# STM32-PROX_2.net
KiCad netlist of a schematic drawn in Altium Designer
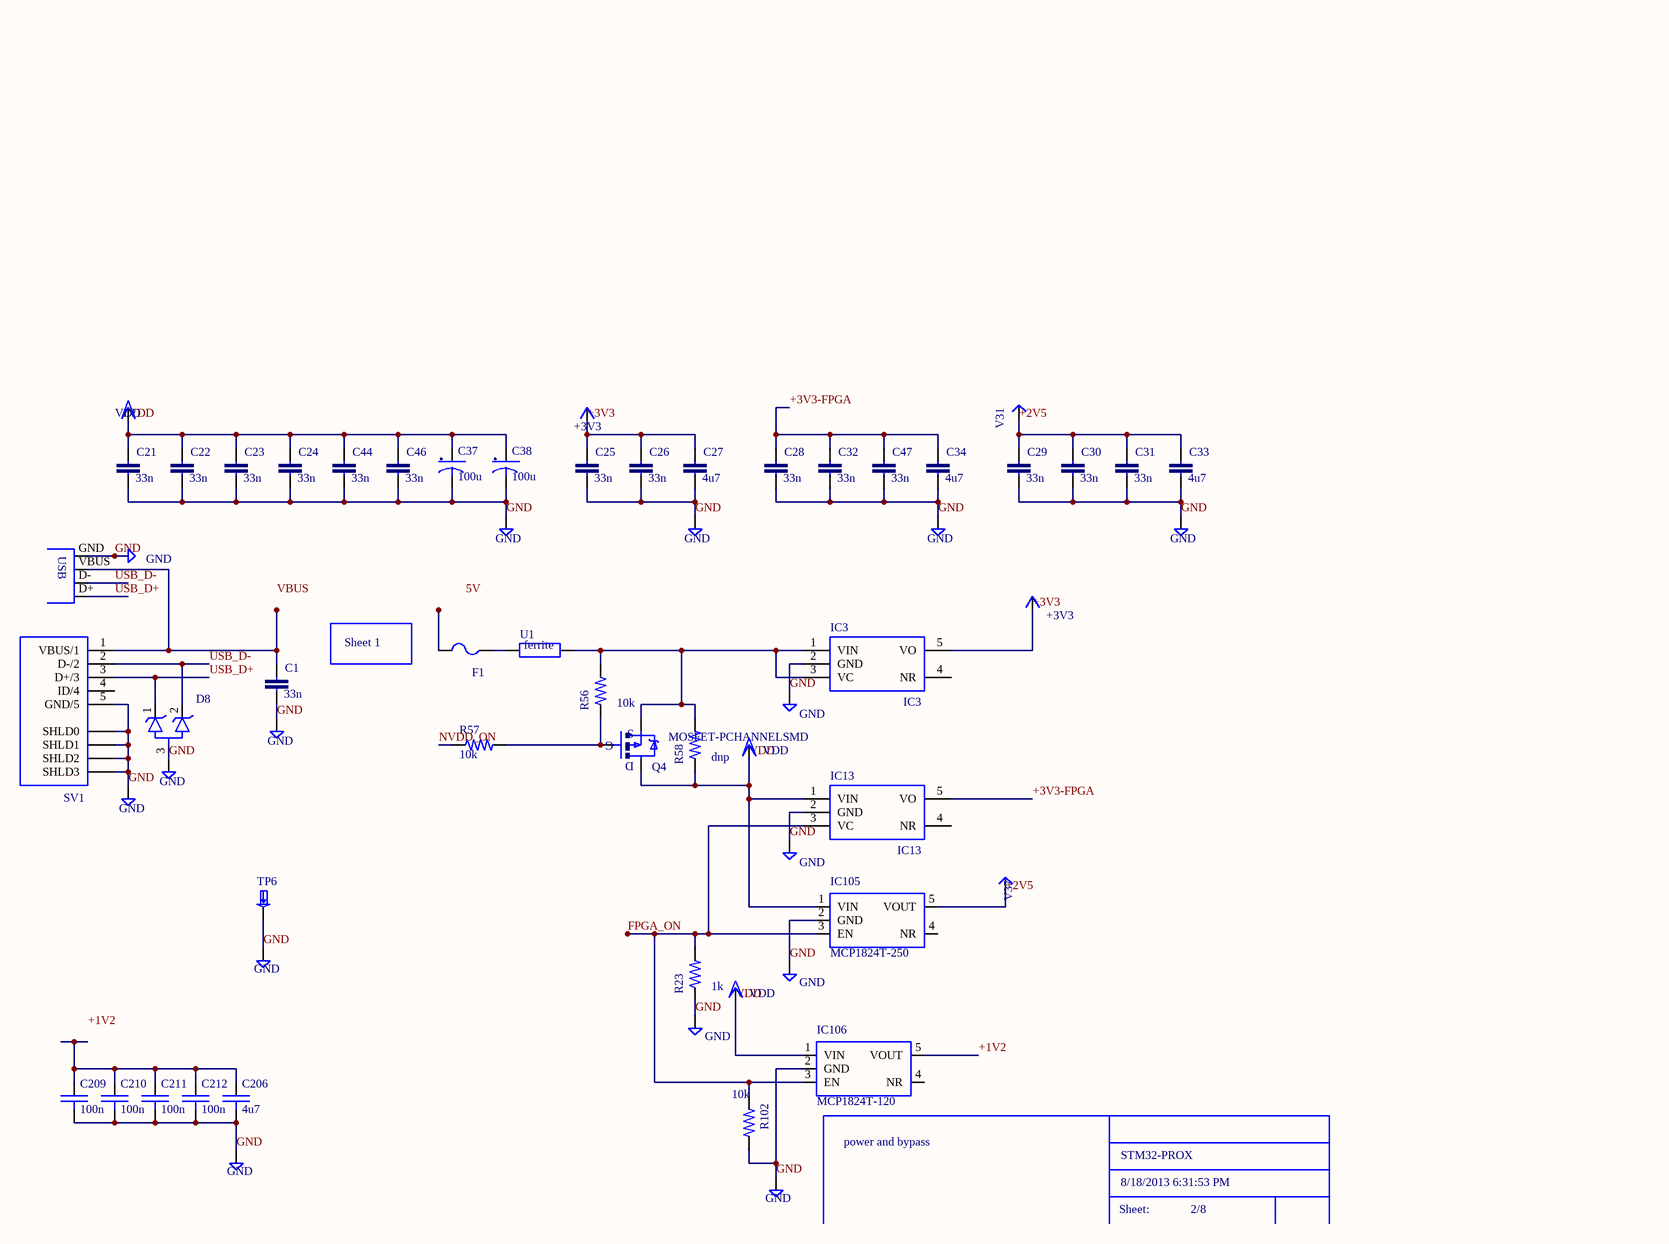
[diagram p0: STM32-PROX_2.SchDoc]

(export (version "E")
  (design (tool "Eeschema 10.0.6"))
  (components
    (comp (ref "C1")
      (value "33n")
      (footprint "RLC_0603")
      (libsource (lib "STM32-PROX") (part "CAPACITORRLC_0603"))
    )
    (comp (ref "C21")
      (value "33n")
      (footprint "RLC_0603")
      (libsource (lib "STM32-PROX") (part "CAPACITORRLC_0603"))
    )
    (comp (ref "C22")
      (value "33n")
      (footprint "RLC_0603")
      (libsource (lib "STM32-PROX") (part "CAPACITORRLC_0603"))
    )
    (comp (ref "C23")
      (value "33n")
      (footprint "RLC_0603")
      (libsource (lib "STM32-PROX") (part "CAPACITORRLC_0603"))
    )
    (comp (ref "C24")
      (value "33n")
      (footprint "RLC_0603")
      (libsource (lib "STM32-PROX") (part "CAPACITORRLC_0603"))
    )
    (comp (ref "C25")
      (value "33n")
      (footprint "RLC_0603")
      (libsource (lib "STM32-PROX") (part "CAPACITORRLC_0603"))
    )
    (comp (ref "C26")
      (value "33n")
      (footprint "RLC_0603")
      (libsource (lib "STM32-PROX") (part "CAPACITORRLC_0603"))
    )
    (comp (ref "C27")
      (value "4u7")
      (footprint "RLC_1210")
      (libsource (lib "STM32-PROX") (part "CAPACITOR1210"))
    )
    (comp (ref "C28")
      (value "33n")
      (footprint "RLC_0603")
      (libsource (lib "STM32-PROX") (part "CAPACITORRLC_0603"))
    )
    (comp (ref "C29")
      (value "33n")
      (footprint "RLC_0603")
      (libsource (lib "STM32-PROX") (part "CAPACITORRLC_0603"))
    )
    (comp (ref "C30")
      (value "33n")
      (footprint "RLC_0603")
      (libsource (lib "STM32-PROX") (part "CAPACITORRLC_0603"))
    )
    (comp (ref "C31")
      (value "33n")
      (footprint "RLC_0603")
      (libsource (lib "STM32-PROX") (part "CAPACITORRLC_0603"))
    )
    (comp (ref "C32")
      (value "33n")
      (footprint "RLC_0603")
      (libsource (lib "STM32-PROX") (part "CAPACITORRLC_0603"))
    )
    (comp (ref "C33")
      (value "4u7")
      (footprint "RLC_1210")
      (libsource (lib "STM32-PROX") (part "CAPACITOR1210"))
    )
    (comp (ref "C34")
      (value "4u7")
      (footprint "RLC_1210")
      (libsource (lib "STM32-PROX") (part "CAPACITOR1210"))
    )
    (comp (ref "C37")
      (value "100u")
      (footprint "D/7343-31R")
      (libsource (lib "STM32-PROX") (part "CPOL-USD/7343-31R"))
    )
    (comp (ref "C38")
      (value "100u")
      (footprint "D/7343-31R")
      (libsource (lib "STM32-PROX") (part "CPOL-USD/7343-31R"))
    )
    (comp (ref "C44")
      (value "33n")
      (footprint "RLC_0603")
      (libsource (lib "STM32-PROX") (part "CAPACITORRLC_0603"))
    )
    (comp (ref "C46")
      (value "33n")
      (footprint "RLC_0603")
      (libsource (lib "STM32-PROX") (part "CAPACITORRLC_0603"))
    )
    (comp (ref "C47")
      (value "33n")
      (footprint "RLC_0603")
      (libsource (lib "STM32-PROX") (part "CAPACITORRLC_0603"))
    )
    (comp (ref "C206") (value "4u7") (footprint "RLC_0603") (libsource (lib "STM32-PROX") (part "C-EU")))
    (comp (ref "C209") (value "100n") (footprint "RLC_0603") (libsource (lib "STM32-PROX") (part "C-EU")))
    (comp (ref "C210") (value "100n") (footprint "RLC_0603") (libsource (lib "STM32-PROX") (part "C-EU")))
    (comp (ref "C211") (value "100n") (footprint "RLC_0603") (libsource (lib "STM32-PROX") (part "C-EU")))
    (comp (ref "C212") (value "100n") (footprint "RLC_0603") (libsource (lib "STM32-PROX") (part "C-EU")))
    (comp (ref "D8")
      (value "~")
      (footprint "SOT23-3LEAD")
      (libsource (lib "STM32-PROX") (part "DUAL-TVS-COMMON-ANODE"))
    )
    (comp (ref "F1") (value "~") (footprint "1812") (libsource (lib "STM32-PROX") (part "PTCFUSE-1812")))
    (comp (ref "FRAME1") (value "~") (libsource (lib "STM32-PROX") (part "A4L-LOC")))
    (comp (ref "IC3")
      (value "~")
      (footprint "SOT-23-5")
      (libsource (lib "STM32-PROX") (part "PQ1X331M2ZP-3V3-LDO-SOT-23-5"))
    )
    (comp (ref "IC13")
      (value "~")
      (footprint "SOT-23-5")
      (libsource (lib "STM32-PROX") (part "PQ1X331M2ZP-3V3-LDO-SOT-23-5"))
    )
    (comp (ref "IC105")
      (value "MCP1824T-250")
      (footprint "SOT-23-5")
      (libsource (lib "STM32-PROX") (part "TPS79925"))
    )
    (comp (ref "IC106")
      (value "MCP1824T-120")
      (footprint "SOT-23-5")
      (libsource (lib "STM32-PROX") (part "TPS79912"))
    )
    (comp (ref "Q4")
      (value "MOSFET-PCHANNELSMD")
      (footprint "SOT23-3")
      (libsource (lib "STM32-PROX") (part "MOSFET-PCHANNELSMD"))
    )
    (comp (ref "R23") (value "1k") (footprint "RLC_0603") (libsource (lib "") (part "RESISTORRLC_0603_1")))
    (comp (ref "R56")
      (value "10k")
      (footprint "RLC_0603")
      (libsource (lib "STM32-PROX") (part "RESISTORRLC_0603"))
    )
    (comp (ref "R57")
      (value "10k")
      (footprint "RLC_0603")
      (libsource (lib "STM32-PROX") (part "RESISTORRLC_0603"))
    )
    (comp (ref "R58")
      (value "dnp")
      (footprint "RLC_0603")
      (libsource (lib "STM32-PROX") (part "RESISTORRLC_0603"))
    )
    (comp (ref "R102")
      (value "10k")
      (footprint "RLC_0603")
      (libsource (lib "STM32-PROX") (part "RESISTORRLC_0603"))
    )
    (comp (ref "SV1")
      (value "~")
      (footprint "USB-MINIB-SMD")
      (libsource (lib "STM32-PROX") (part "USB-MINIB"))
    )
    (comp (ref "TP6")
      (value "~")
      (footprint "KEYSTONE-PTH-TESTPOINT-5011")
      (libsource (lib "STM32-PROX") (part "TESTPADKEYSTONE-PTH"))
    )
    (comp (ref "U$3") (value "+3V3") (libsource (lib "STM32-PROX") (part "+3V3")))
    (comp (ref "U$8") (value "+3V3") (libsource (lib "STM32-PROX") (part "+3V3")))
    (comp (ref "U1") (value "~") (footprint "RLC_0805") (libsource (lib "STM32-PROX") (part "FERRITE0805")))
    (comp (ref "USB-MICRO")
      (value "~")
      (footprint "USB-MICROB")
      (libsource (lib "SparkFun") (part "USB-MICROB"))
    )
    (comp (ref "V1") (value "GND") (libsource (lib "STM32-PROX") (part "GND")))
    (comp (ref "V2") (value "GND") (libsource (lib "STM32-PROX") (part "GND")))
    (comp (ref "V3") (value "GND") (libsource (lib "STM32-PROX") (part "GND")))
    (comp (ref "V4") (value "GND") (libsource (lib "STM32-PROX") (part "GND")))
    (comp (ref "V6") (value "GND") (libsource (lib "STM32-PROX") (part "GND")))
    (comp (ref "V8") (value "GND") (libsource (lib "STM32-PROX") (part "GND")))
    (comp (ref "V29") (value "GND") (libsource (lib "STM32-PROX") (part "GND")))
    (comp (ref "V30") (value "GND") (libsource (lib "STM32-PROX") (part "GND")))
    (comp (ref "V31") (value "~") (libsource (lib "STM32-PROX") (part "SUPPLY_2V5")))
    (comp (ref "V32") (value "GND") (libsource (lib "STM32-PROX") (part "GND")))
    (comp (ref "V35") (value "GND") (libsource (lib "STM32-PROX") (part "GND")))
    (comp (ref "V36") (value "GND") (libsource (lib "STM32-PROX") (part "GND")))
    (comp (ref "V37") (value "~") (libsource (lib "STM32-PROX") (part "SUPPLY_2V5")))
    (comp (ref "V38") (value "GND") (libsource (lib "STM32-PROX") (part "GND")))
    (comp (ref "V39") (value "GND") (libsource (lib "STM32-PROX") (part "GND")))
    (comp (ref "V51") (value "GND") (libsource (lib "STM32-PROX") (part "GND")))
    (comp (ref "V54") (value "GND") (libsource (lib "STM32-PROX") (part "GND")))
    (comp (ref "VDD1") (value "VDD") (libsource (lib "") (part "VDD_1")))
    (comp (ref "VDD7") (value "VDD") (libsource (lib "") (part "VDD_1")))
    (comp (ref "VDD12") (value "VDD") (libsource (lib "STM32-PROX") (part "VDD")))
  )
  (nets
    (net (code "1") (name "/+1V2") (class "Default")
      (node (ref "IC106") (pin "5") (pinfunction "VOUT_5") (pintype "passive"))
    )
    (net (code "2") (name "/+2V5") (class "Default")
      (node (ref "C29") (pin "1") (pinfunction "1_1") (pintype "passive"))
      (node (ref "C30") (pin "1") (pinfunction "1_1") (pintype "passive"))
      (node (ref "C31") (pin "1") (pinfunction "1_1") (pintype "passive"))
      (node (ref "C33") (pin "1") (pinfunction "1_1") (pintype "passive"))
      (node (ref "IC105") (pin "5") (pinfunction "VOUT_5") (pintype "passive"))
      (node (ref "V31") (pin "0") (pinfunction "+2V5_0") (pintype "passive"))
      (node (ref "V37") (pin "0") (pinfunction "+2V5_0") (pintype "passive"))
    )
    (net (code "3") (name "/+3V3") (class "Default")
      (node (ref "C25") (pin "1") (pinfunction "1_1") (pintype "passive"))
      (node (ref "C26") (pin "1") (pinfunction "1_1") (pintype "passive"))
      (node (ref "C27") (pin "1") (pinfunction "1_1") (pintype "passive"))
      (node (ref "IC3") (pin "5") (pinfunction "VO_5") (pintype "passive"))
      (node (ref "U$3") (pin "0") (pinfunction "+3V3_0") (pintype "passive"))
      (node (ref "U$8") (pin "0") (pinfunction "+3V3_0") (pintype "passive"))
    )
    (net (code "4") (name "/+3V3-FPGA") (class "Default")
      (node (ref "C28") (pin "1") (pinfunction "1_1") (pintype "passive"))
      (node (ref "C32") (pin "1") (pinfunction "1_1") (pintype "passive"))
      (node (ref "C34") (pin "1") (pinfunction "1_1") (pintype "passive"))
      (node (ref "C47") (pin "1") (pinfunction "1_1") (pintype "passive"))
      (node (ref "IC13") (pin "5") (pinfunction "VO_5") (pintype "passive"))
    )
    (net (code "6") (name "/FPGA_ON") (class "Default")
      (node (ref "IC105") (pin "3") (pinfunction "EN_3") (pintype "passive"))
      (node (ref "IC106") (pin "3") (pinfunction "EN_3") (pintype "passive"))
      (node (ref "IC13") (pin "3") (pinfunction "VC_3") (pintype "passive"))
      (node (ref "R102") (pin "1") (pinfunction "1_1") (pintype "passive"))
      (node (ref "R23") (pin "2") (pinfunction "2_2") (pintype "passive"))
    )
    (net (code "7") (name "/GND") (class "Default")
      (node (ref "C1") (pin "2") (pinfunction "2_2") (pintype "passive"))
      (node (ref "C206") (pin "2") (pinfunction "2_2") (pintype "passive"))
      (node (ref "C209") (pin "2") (pinfunction "2_2") (pintype "passive"))
      (node (ref "C21") (pin "2") (pinfunction "2_2") (pintype "passive"))
      (node (ref "C210") (pin "2") (pinfunction "2_2") (pintype "passive"))
      (node (ref "C211") (pin "2") (pinfunction "2_2") (pintype "passive"))
      (node (ref "C212") (pin "2") (pinfunction "2_2") (pintype "passive"))
      (node (ref "C22") (pin "2") (pinfunction "2_2") (pintype "passive"))
      (node (ref "C23") (pin "2") (pinfunction "2_2") (pintype "passive"))
      (node (ref "C24") (pin "2") (pinfunction "2_2") (pintype "passive"))
      (node (ref "C25") (pin "2") (pinfunction "2_2") (pintype "passive"))
      (node (ref "C26") (pin "2") (pinfunction "2_2") (pintype "passive"))
      (node (ref "C27") (pin "2") (pinfunction "2_2") (pintype "passive"))
      (node (ref "C28") (pin "2") (pinfunction "2_2") (pintype "passive"))
      (node (ref "C29") (pin "2") (pinfunction "2_2") (pintype "passive"))
      (node (ref "C30") (pin "2") (pinfunction "2_2") (pintype "passive"))
      (node (ref "C31") (pin "2") (pinfunction "2_2") (pintype "passive"))
      (node (ref "C32") (pin "2") (pinfunction "2_2") (pintype "passive"))
      (node (ref "C33") (pin "2") (pinfunction "2_2") (pintype "passive"))
      (node (ref "C34") (pin "2") (pinfunction "2_2") (pintype "passive"))
      (node (ref "C37") (pin "-") (pinfunction "-_-") (pintype "passive"))
      (node (ref "C38") (pin "-") (pinfunction "-_-") (pintype "passive"))
      (node (ref "C44") (pin "2") (pinfunction "2_2") (pintype "passive"))
      (node (ref "C46") (pin "2") (pinfunction "2_2") (pintype "passive"))
      (node (ref "C47") (pin "2") (pinfunction "2_2") (pintype "passive"))
      (node (ref "D8") (pin "3") (pinfunction "A_3") (pintype "passive"))
      (node (ref "IC105") (pin "2") (pinfunction "GND_2") (pintype "passive"))
      (node (ref "IC106") (pin "2") (pinfunction "GND_2") (pintype "passive"))
      (node (ref "IC13") (pin "2") (pinfunction "GND_2") (pintype "passive"))
      (node (ref "IC3") (pin "2") (pinfunction "GND_2") (pintype "passive"))
      (node (ref "R102") (pin "2") (pinfunction "2_2") (pintype "passive"))
      (node (ref "R23") (pin "1") (pinfunction "1_1") (pintype "passive"))
      (node (ref "SV1") (pin "5") (pinfunction "GND/5_5") (pintype "passive"))
      (node (ref "SV1") (pin "TAB0") (pinfunction "SHLD0_TAB0") (pintype "passive"))
      (node (ref "SV1") (pin "TAB1") (pinfunction "SHLD1_TAB1") (pintype "passive"))
      (node (ref "SV1") (pin "TAB2") (pinfunction "SHLD2_TAB2") (pintype "passive"))
      (node (ref "SV1") (pin "TAB3") (pinfunction "SHLD3_TAB3") (pintype "passive"))
      (node (ref "TP6") (pin "A") (pinfunction "P$1_A") (pintype "passive"))
      (node (ref "USB-MICRO") (pin "GND") (pinfunction "GND_GND") (pintype "passive"))
      (node (ref "V1") (pin "0") (pinfunction "GND_0") (pintype "passive"))
      (node (ref "V2") (pin "0") (pinfunction "GND_0") (pintype "passive"))
      (node (ref "V29") (pin "0") (pinfunction "GND_0") (pintype "passive"))
      (node (ref "V3") (pin "0") (pinfunction "GND_0") (pintype "passive"))
      (node (ref "V30") (pin "0") (pinfunction "GND_0") (pintype "passive"))
      (node (ref "V32") (pin "0") (pinfunction "GND_0") (pintype "passive"))
      (node (ref "V35") (pin "0") (pinfunction "GND_0") (pintype "passive"))
      (node (ref "V36") (pin "0") (pinfunction "GND_0") (pintype "passive"))
      (node (ref "V38") (pin "0") (pinfunction "GND_0") (pintype "passive"))
      (node (ref "V39") (pin "0") (pinfunction "GND_0") (pintype "passive"))
      (node (ref "V4") (pin "0") (pinfunction "GND_0") (pintype "passive"))
      (node (ref "V51") (pin "0") (pinfunction "GND_0") (pintype "passive"))
      (node (ref "V54") (pin "0") (pinfunction "GND_0") (pintype "passive"))
      (node (ref "V6") (pin "0") (pinfunction "GND_0") (pintype "passive"))
      (node (ref "V8") (pin "0") (pinfunction "GND_0") (pintype "passive"))
    )
    (net (code "8") (name "/NVDD_ON") (class "Default")
      (node (ref "R57") (pin "1") (pinfunction "1_1") (pintype "passive"))
    )
    (net (code "9") (name "/USB_D+") (class "Default")
      (node (ref "D8") (pin "1") (pinfunction "K1_1") (pintype "passive"))
      (node (ref "SV1") (pin "3") (pinfunction "D+/3_3") (pintype "passive"))
      (node (ref "USB-MICRO") (pin "D+") (pinfunction "D+_D+") (pintype "passive"))
    )
    (net (code "10") (name "/USB_D-") (class "Default")
      (node (ref "D8") (pin "2") (pinfunction "K2_2") (pintype "passive"))
      (node (ref "SV1") (pin "2") (pinfunction "D-/2_2") (pintype "passive"))
      (node (ref "USB-MICRO") (pin "D-") (pinfunction "D-_D-") (pintype "passive"))
    )
    (net (code "12") (name "/VDD") (class "Default")
      (node (ref "C21") (pin "1") (pinfunction "1_1") (pintype "passive"))
      (node (ref "C22") (pin "1") (pinfunction "1_1") (pintype "passive"))
      (node (ref "C23") (pin "1") (pinfunction "1_1") (pintype "passive"))
      (node (ref "C24") (pin "1") (pinfunction "1_1") (pintype "passive"))
      (node (ref "C37") (pin "+") (pinfunction "+_+") (pintype "passive"))
      (node (ref "C38") (pin "+") (pinfunction "+_+") (pintype "passive"))
      (node (ref "C44") (pin "1") (pinfunction "1_1") (pintype "passive"))
      (node (ref "C46") (pin "1") (pinfunction "1_1") (pintype "passive"))
      (node (ref "IC105") (pin "1") (pinfunction "VIN_1") (pintype "passive"))
      (node (ref "IC106") (pin "1") (pinfunction "VIN_1") (pintype "passive"))
      (node (ref "IC13") (pin "1") (pinfunction "VIN_1") (pintype "passive"))
      (node (ref "Q4") (pin "3") (pinfunction "D_3") (pintype "passive"))
      (node (ref "R58") (pin "1") (pinfunction "1_1") (pintype "passive"))
      (node (ref "VDD1") (pin "0") (pinfunction "VDD_0") (pintype "passive"))
      (node (ref "VDD12") (pin "0") (pinfunction "VDD_0") (pintype "passive"))
      (node (ref "VDD7") (pin "0") (pinfunction "VDD_0") (pintype "passive"))
    )
    (net (code "13") (name "Net-(C206-Pad1)") (class "Default")
      (node (ref "C206") (pin "1") (pinfunction "1_1") (pintype "passive"))
      (node (ref "C209") (pin "1") (pinfunction "1_1") (pintype "passive"))
      (node (ref "C210") (pin "1") (pinfunction "1_1") (pintype "passive"))
      (node (ref "C211") (pin "1") (pinfunction "1_1") (pintype "passive"))
      (node (ref "C212") (pin "1") (pinfunction "1_1") (pintype "passive"))
    )
    (net (code "14") (name "Net-(IC3-VC)") (class "Default")
      (node (ref "IC3") (pin "1") (pinfunction "VIN_1") (pintype "passive"))
      (node (ref "IC3") (pin "3") (pinfunction "VC_3") (pintype "passive"))
      (node (ref "Q4") (pin "2") (pinfunction "S_2") (pintype "passive"))
      (node (ref "R56") (pin "2") (pinfunction "2_2") (pintype "passive"))
      (node (ref "R58") (pin "2") (pinfunction "2_2") (pintype "passive"))
      (node (ref "U1") (pin "2") (pinfunction "B_2") (pintype "passive"))
    )
    (net (code "15") (name "Net-(Q4-G)") (class "Default")
      (node (ref "Q4") (pin "1") (pinfunction "G_1") (pintype "passive"))
      (node (ref "R56") (pin "1") (pinfunction "1_1") (pintype "passive"))
      (node (ref "R57") (pin "2") (pinfunction "2_2") (pintype "passive"))
    )
    (net (code "16") (name "Net-(SV1-VBUS{slash}1)") (class "Default")
      (node (ref "C1") (pin "1") (pinfunction "1_1") (pintype "passive"))
      (node (ref "SV1") (pin "1") (pinfunction "VBUS/1_1") (pintype "passive"))
      (node (ref "USB-MICRO") (pin "VBUS") (pinfunction "VBUS_VBUS") (pintype "passive"))
    )
    (net (code "17") (name "Net-(U1-A)") (class "Default")
      (node (ref "F1") (pin "1") (pinfunction "1_1") (pintype "passive"))
      (node (ref "U1") (pin "1") (pinfunction "A_1") (pintype "passive"))
    )
    (net (code "18") (name "unconnected-(F1-Pad2)") (class "Default")
      (node (ref "F1") (pin "2") (pinfunction "2_2") (pintype "passive"))
    )
    (net (code "19") (name "unconnected-(IC3-NR-Pad4)") (class "Default")
      (node (ref "IC3") (pin "4") (pinfunction "NR_4") (pintype "passive"))
    )
    (net (code "20") (name "unconnected-(IC13-NR-Pad4)") (class "Default")
      (node (ref "IC13") (pin "4") (pinfunction "NR_4") (pintype "passive"))
    )
    (net (code "21") (name "unconnected-(IC105-NR-Pad4)") (class "Default")
      (node (ref "IC105") (pin "4") (pinfunction "NR_4") (pintype "passive"))
    )
    (net (code "22") (name "unconnected-(IC106-NR-Pad4)") (class "Default")
      (node (ref "IC106") (pin "4") (pinfunction "NR_4") (pintype "passive"))
    )
    (net (code "23") (name "unconnected-(SV1-ID{slash}4-Pad4)") (class "Default")
      (node (ref "SV1") (pin "4") (pinfunction "ID/4_4") (pintype "passive"))
    )
  )
)
